# Sheet1.net
KiCad netlist of a schematic drawn in Altium Designer
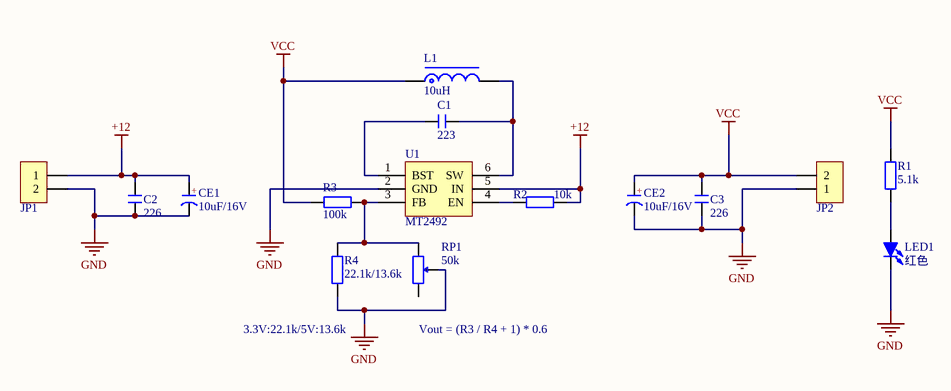
[diagram p0: Sheet1.SchDoc]

(export (version "E")
  (design (tool "Eeschema 10.0.6"))
  (components
    (comp (ref "C1")
      (value "223")
      (footprint "C 0805-M")
      (description "贴片电容")
      (libsource (lib "0.1 - 电阻-电容-电感") (part "C"))
    )
    (comp (ref "C2")
      (value "226")
      (footprint "C 0805-M")
      (description "贴片电容")
      (libsource (lib "0.1 - 电阻-电容-电感") (part "C"))
    )
    (comp (ref "C3")
      (value "226")
      (footprint "C 0805-M")
      (description "贴片电容")
      (libsource (lib "0.1 - 电阻-电容-电感") (part "C"))
    )
    (comp (ref "CE1")
      (value "10uF/16V")
      (footprint "CAP 1.5*4*8")
      (description "直插电解电容")
      (libsource (lib "0.1 - 电阻-电容-电感") (part "CE"))
    )
    (comp (ref "CE2")
      (value "10uF/16V")
      (footprint "CAP 1.5*4*8")
      (description "直插电解电容")
      (libsource (lib "0.1 - 电阻-电容-电感") (part "CE"))
    )
    (comp (ref "JP1")
      (value "HDR-1X2")
      (footprint "KF2EDGK5.0-LI-2P")
      (description "2P接插件")
      (fields (field (name "版权归属") "封装库来自淘宝 ID：黄晶宝石"))
      (libsource (lib "") (part "Header 2_1"))
    )
    (comp (ref "JP2")
      (value "HDR-1X2")
      (footprint "KF2EDGK5.0-LI-2P")
      (description "2P接插件")
      (fields (field (name "版权归属") "封装库来自淘宝 ID：黄晶宝石"))
      (libsource (lib "6.0 - 接插件-脚距5.0") (part "Header 2"))
    )
    (comp (ref "L1")
      (value "10uH")
      (footprint "L-SMD-0630")
      (description "NR磁胶电感")
      (libsource (lib "0.1 - 电阻-电容-电感") (part "L-NR"))
    )
    (comp (ref "LED1")
      (value "红色")
      (footprint "LED 0805G")
      (description "贴片LED")
      (libsource (lib "0.3 - LED发光二极管") (part "LED-SMD"))
    )
    (comp (ref "R1")
      (value "5.1k")
      (footprint "R 0805_L")
      (description "贴片电阻")
      (libsource (lib "0.1 - 电阻-电容-电感") (part "R"))
    )
    (comp (ref "R2")
      (value "10k")
      (footprint "R 0805_L")
      (description "贴片电阻")
      (libsource (lib "0.1 - 电阻-电容-电感") (part "R"))
    )
    (comp (ref "R3")
      (value "100k")
      (footprint "R 0805_L")
      (description "贴片电阻")
      (libsource (lib "0.1 - 电阻-电容-电感") (part "R"))
    )
    (comp (ref "R4")
      (value "22.1k/13.6k")
      (footprint "R 0805_L")
      (description "贴片电阻")
      (libsource (lib "0.1 - 电阻-电容-电感") (part "R"))
    )
    (comp (ref "RP1")
      (value "50k")
      (footprint "3303W")
      (description "贴片电位器")
      (libsource (lib "0.1 - 电阻-电容-电感") (part "RP-SMD"))
    )
    (comp (ref "U1")
      (value "MT2492")
      (footprint "SOT23-6N")
      (description "DC降压芯片")
      (libsource (lib "1.0 - 电源类芯片") (part "MP2359"))
    )
  )
  (nets
    (net (code "1") (name "+12") (class "Default")
      (node (ref "C2") (pin "2") (pinfunction "2_2") (pintype "passive"))
      (node (ref "CE1") (pin "1") (pinfunction "A_1") (pintype "passive"))
      (node (ref "JP1") (pin "1") (pinfunction "1_1") (pintype "passive"))
      (node (ref "R2") (pin "2") (pinfunction "2_2") (pintype "passive"))
      (node (ref "U1") (pin "5") (pinfunction "IN_5") (pintype "passive"))
    )
    (net (code "2") (name "GND") (class "Default")
      (node (ref "C2") (pin "1") (pinfunction "1_1") (pintype "passive"))
      (node (ref "C3") (pin "1") (pinfunction "1_1") (pintype "passive"))
      (node (ref "CE1") (pin "2") (pinfunction "K_2") (pintype "passive"))
      (node (ref "CE2") (pin "2") (pinfunction "K_2") (pintype "passive"))
      (node (ref "JP1") (pin "2") (pinfunction "2_2") (pintype "passive"))
      (node (ref "JP2") (pin "1") (pinfunction "1_1") (pintype "passive"))
      (node (ref "LED1") (pin "2") (pinfunction "K_2") (pintype "passive"))
      (node (ref "R4") (pin "1") (pinfunction "1_1") (pintype "passive"))
      (node (ref "RP1") (pin "2") (pinfunction "2_2") (pintype "passive"))
      (node (ref "U1") (pin "2") (pinfunction "GND_2") (pintype "passive"))
    )
    (net (code "3") (name "Net-(LED1-A)") (class "Default")
      (node (ref "LED1") (pin "1") (pinfunction "A_1") (pintype "passive"))
      (node (ref "R1") (pin "1") (pinfunction "1_1") (pintype "passive"))
    )
    (net (code "4") (name "Net-(U1-BST)") (class "Default")
      (node (ref "C1") (pin "2") (pinfunction "2_2") (pintype "passive"))
      (node (ref "U1") (pin "1") (pinfunction "BST_1") (pintype "passive"))
    )
    (net (code "5") (name "Net-(U1-EN)") (class "Default")
      (node (ref "R2") (pin "1") (pinfunction "1_1") (pintype "passive"))
      (node (ref "U1") (pin "4") (pinfunction "EN_4") (pintype "passive"))
    )
    (net (code "6") (name "Net-(U1-FB)") (class "Default")
      (node (ref "R3") (pin "2") (pinfunction "2_2") (pintype "passive"))
      (node (ref "R4") (pin "2") (pinfunction "2_2") (pintype "passive"))
      (node (ref "RP1") (pin "1") (pinfunction "1_1") (pintype "passive"))
      (node (ref "U1") (pin "3") (pinfunction "FB_3") (pintype "passive"))
    )
    (net (code "7") (name "Net-(U1-SW)") (class "Default")
      (node (ref "C1") (pin "1") (pinfunction "1_1") (pintype "passive"))
      (node (ref "L1") (pin "2") (pinfunction "2_2") (pintype "passive"))
      (node (ref "U1") (pin "6") (pinfunction "SW_6") (pintype "passive"))
    )
    (net (code "8") (name "VCC") (class "Default")
      (node (ref "C3") (pin "2") (pinfunction "2_2") (pintype "passive"))
      (node (ref "CE2") (pin "1") (pinfunction "A_1") (pintype "passive"))
      (node (ref "JP2") (pin "2") (pinfunction "2_2") (pintype "passive"))
      (node (ref "L1") (pin "1") (pinfunction "1_1") (pintype "passive"))
      (node (ref "R1") (pin "2") (pinfunction "2_2") (pintype "passive"))
      (node (ref "R3") (pin "1") (pinfunction "1_1") (pintype "passive"))
    )
    (net (code "9") (name "unconnected-(RP1-Pad3)") (class "Default")
      (node (ref "RP1") (pin "3") (pinfunction "3_3") (pintype "passive"))
    )
  )
)
